# LCD.net
KiCad netlist of a schematic drawn in Altium Designer
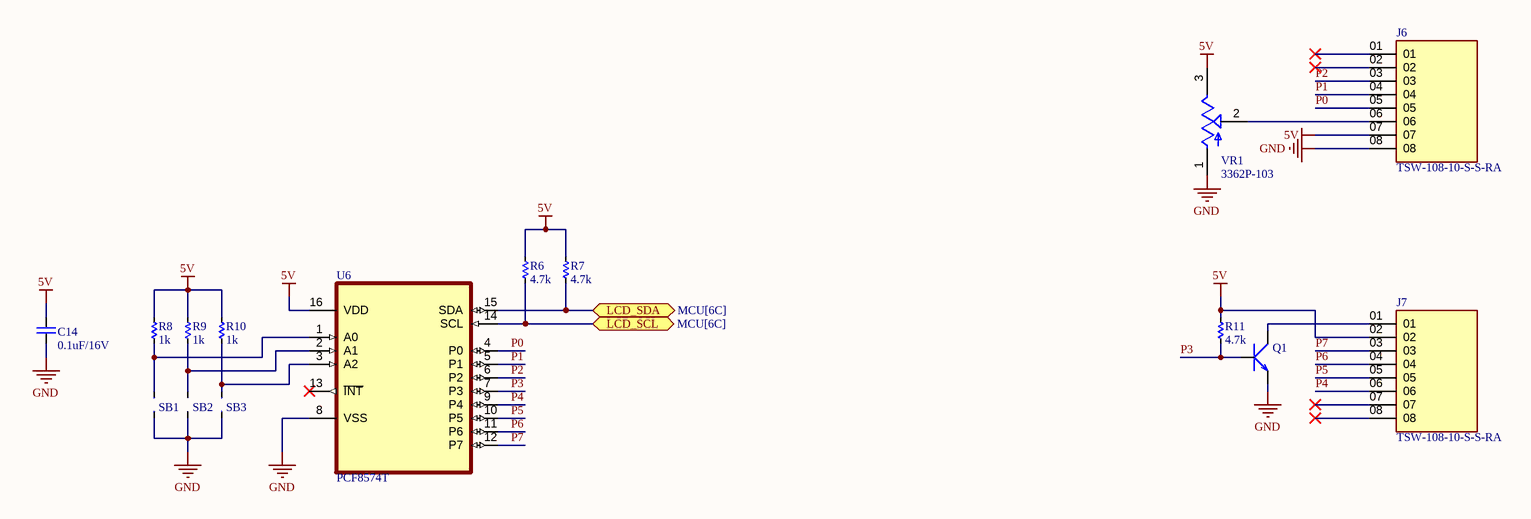
[diagram p0: LCD.SchDoc]

(export (version "E")
  (design (tool "Eeschema 10.0.6"))
  (components
    (comp (ref "C14")
      (value "0.1uF/16V")
      (footprint "CAP_C_1608X80")
      (description "CAP_Chip")
      (libsource (lib "BTL_SCHLIB") (part "CAP_SMD"))
    )
    (comp (ref "J6")
      (value "TSW-108-10-S-S-RA")
      (footprint "SAMTEC_TSW-108-10-S-S-RA")
      (description "Connector Header Through Hole, Right Angle 8 position 0.100 (2.54mm)")
      (fields (field (name "MF") "Samtec"))
      (libsource (lib "BTL_SCHLIB") (part "TSW-108-10-S-S-RA"))
    )
    (comp (ref "J7")
      (value "TSW-108-10-S-S-RA")
      (footprint "SAMTEC_TSW-108-10-S-S-RA")
      (description "Connector Header Through Hole, Right Angle 8 position 0.100 (2.54mm)")
      (fields (field (name "MF") "Samtec"))
      (libsource (lib "BTL_SCHLIB") (part "TSW-108-10-S-S-RA"))
    )
    (comp (ref "Q1")
      (value "SMD-TRANSISTORS-NPN-25V-500MW(SOT-23)")
      (footprint "SOT-23")
      (description "Bipolar (BJT) Transistor NPN 25 V 500 mA 150MHz 300 mW Surface Mount SOT-23")
      (fields (field (name "MF") "UMW") (field (name "MP") "S8050"))
      (libsource (lib "BTL_SCHLIB") (part "SMD-TRANSISTORS-NPN-25V-500MW(SOT-23)"))
    )
    (comp (ref "R6")
      (value "4.7k")
      (footprint "RES_C_1608X60")
      (description "RES")
      (libsource (lib "BTL_SCHLIB") (part "RES_SMD"))
    )
    (comp (ref "R7")
      (value "4.7k")
      (footprint "RES_C_1608X60")
      (description "RES")
      (libsource (lib "BTL_SCHLIB") (part "RES_SMD"))
    )
    (comp (ref "R8")
      (value "1k")
      (footprint "RES_C_1608X60")
      (description "RES")
      (libsource (lib "BTL_SCHLIB") (part "RES_SMD"))
    )
    (comp (ref "R9")
      (value "1k")
      (footprint "RES_C_1608X60")
      (description "RES")
      (libsource (lib "BTL_SCHLIB") (part "RES_SMD"))
    )
    (comp (ref "R10")
      (value "1k")
      (footprint "RES_C_1608X60")
      (description "RES")
      (libsource (lib "BTL_SCHLIB") (part "RES_SMD"))
    )
    (comp (ref "R11")
      (value "4.7k")
      (footprint "RES_C_1608X60")
      (description "RES")
      (libsource (lib "BTL_SCHLIB") (part "RES_SMD"))
    )
    (comp (ref "SB1")
      (value "JUMPER")
      (footprint "JUMPER_1608")
      (libsource (lib "BTL_SCHLIB") (part "JUMPER"))
    )
    (comp (ref "SB2")
      (value "JUMPER")
      (footprint "JUMPER_1608")
      (libsource (lib "BTL_SCHLIB") (part "JUMPER"))
    )
    (comp (ref "SB3")
      (value "JUMPER")
      (footprint "JUMPER_1608")
      (libsource (lib "BTL_SCHLIB") (part "JUMPER"))
    )
    (comp (ref "U6")
      (value "PCF8574T")
      (footprint "SOIC127P1032X265-16N")
      (description "I/O Expander 8 IÂ²C 100 kHz 20-SSOP")
      (fields (field (name "MF") "NXP Semiconductors"))
      (libsource (lib "BTL_SCHLIB") (part "PCF8574T"))
    )
    (comp (ref "VR1")
      (value "3362P-103")
      (footprint "TRIM_3362P-103")
      (description "10 kOhms 0.5W, 1/2W PC Pins Through Hole Trimmer Potentiometer Cermet 1 Turn Top Finger Adjustment")
      (fields (field (name "MF") "Bourns"))
      (libsource (lib "BTL_SCHLIB") (part "3362P-103"))
    )
  )
  (nets
    (net (code "1") (name "/LCD_SCL") (class "Default")
      (node (ref "R6") (pin "1") (pinfunction "1_1") (pintype "passive"))
      (node (ref "U6") (pin "14") (pinfunction "SCL_14") (pintype "input"))
    )
    (net (code "2") (name "/LCD_SDA") (class "Default")
      (node (ref "R7") (pin "1") (pinfunction "1_1") (pintype "passive"))
      (node (ref "U6") (pin "15") (pinfunction "SDA_15") (pintype "bidirectional"))
    )
    (net (code "3") (name "/P0") (class "Default")
      (node (ref "J6") (pin "05") (pinfunction "05_05") (pintype "passive"))
      (node (ref "U6") (pin "4") (pinfunction "P0_4") (pintype "bidirectional"))
    )
    (net (code "4") (name "/P1") (class "Default")
      (node (ref "J6") (pin "04") (pinfunction "04_04") (pintype "passive"))
      (node (ref "U6") (pin "5") (pinfunction "P1_5") (pintype "bidirectional"))
    )
    (net (code "5") (name "/P2") (class "Default")
      (node (ref "J6") (pin "03") (pinfunction "03_03") (pintype "passive"))
      (node (ref "U6") (pin "6") (pinfunction "P2_6") (pintype "bidirectional"))
    )
    (net (code "6") (name "/P3") (class "Default")
      (node (ref "Q1") (pin "1") (pinfunction "B_1") (pintype "passive"))
      (node (ref "R11") (pin "1") (pinfunction "1_1") (pintype "passive"))
      (node (ref "U6") (pin "7") (pinfunction "P3_7") (pintype "bidirectional"))
    )
    (net (code "7") (name "/P4") (class "Default")
      (node (ref "J7") (pin "06") (pinfunction "06_06") (pintype "passive"))
      (node (ref "U6") (pin "9") (pinfunction "P4_9") (pintype "bidirectional"))
    )
    (net (code "8") (name "/P5") (class "Default")
      (node (ref "J7") (pin "05") (pinfunction "05_05") (pintype "passive"))
      (node (ref "U6") (pin "10") (pinfunction "P5_10") (pintype "bidirectional"))
    )
    (net (code "9") (name "/P6") (class "Default")
      (node (ref "J7") (pin "04") (pinfunction "04_04") (pintype "passive"))
      (node (ref "U6") (pin "11") (pinfunction "P6_11") (pintype "bidirectional"))
    )
    (net (code "10") (name "/P7") (class "Default")
      (node (ref "J7") (pin "03") (pinfunction "03_03") (pintype "passive"))
      (node (ref "U6") (pin "12") (pinfunction "P7_12") (pintype "bidirectional"))
    )
    (net (code "11") (name "5V") (class "Default")
      (node (ref "C14") (pin "2") (pinfunction "2_2") (pintype "passive"))
      (node (ref "J6") (pin "07") (pinfunction "07_07") (pintype "passive"))
      (node (ref "J7") (pin "02") (pinfunction "02_02") (pintype "passive"))
      (node (ref "R10") (pin "2") (pinfunction "2_2") (pintype "passive"))
      (node (ref "R11") (pin "2") (pinfunction "2_2") (pintype "passive"))
      (node (ref "R6") (pin "2") (pinfunction "2_2") (pintype "passive"))
      (node (ref "R7") (pin "2") (pinfunction "2_2") (pintype "passive"))
      (node (ref "R8") (pin "2") (pinfunction "2_2") (pintype "passive"))
      (node (ref "R9") (pin "2") (pinfunction "2_2") (pintype "passive"))
      (node (ref "U6") (pin "16") (pinfunction "VDD_16") (pintype "power_in"))
      (node (ref "VR1") (pin "3") (pinfunction "CW_3") (pintype "passive"))
    )
    (net (code "12") (name "GND") (class "Default")
      (node (ref "C14") (pin "1") (pinfunction "1_1") (pintype "passive"))
      (node (ref "J6") (pin "08") (pinfunction "08_08") (pintype "passive"))
      (node (ref "Q1") (pin "2") (pinfunction "E_2") (pintype "passive"))
      (node (ref "SB1") (pin "1") (pinfunction "1_1") (pintype "passive"))
      (node (ref "SB2") (pin "1") (pinfunction "1_1") (pintype "passive"))
      (node (ref "SB3") (pin "1") (pinfunction "1_1") (pintype "passive"))
      (node (ref "U6") (pin "8") (pinfunction "VSS_8") (pintype "passive"))
      (node (ref "VR1") (pin "1") (pinfunction "CCW_1") (pintype "passive"))
    )
    (net (code "13") (name "Net-(Q1-C)") (class "Default")
      (node (ref "J7") (pin "01") (pinfunction "01_01") (pintype "passive"))
      (node (ref "Q1") (pin "3") (pinfunction "C_3") (pintype "passive"))
    )
    (net (code "14") (name "Net-(U6-A0)") (class "Default")
      (node (ref "R8") (pin "1") (pinfunction "1_1") (pintype "passive"))
      (node (ref "SB1") (pin "2") (pinfunction "2_2") (pintype "passive"))
      (node (ref "U6") (pin "1") (pinfunction "A0_1") (pintype "input"))
    )
    (net (code "15") (name "Net-(U6-A1)") (class "Default")
      (node (ref "R9") (pin "1") (pinfunction "1_1") (pintype "passive"))
      (node (ref "SB2") (pin "2") (pinfunction "2_2") (pintype "passive"))
      (node (ref "U6") (pin "2") (pinfunction "A1_2") (pintype "input"))
    )
    (net (code "16") (name "Net-(U6-A2)") (class "Default")
      (node (ref "R10") (pin "1") (pinfunction "1_1") (pintype "passive"))
      (node (ref "SB3") (pin "2") (pinfunction "2_2") (pintype "passive"))
      (node (ref "U6") (pin "3") (pinfunction "A2_3") (pintype "input"))
    )
    (net (code "17") (name "Net-(VR1-WIPER)") (class "Default")
      (node (ref "J6") (pin "06") (pinfunction "06_06") (pintype "passive"))
      (node (ref "VR1") (pin "2") (pinfunction "WIPER_2") (pintype "passive"))
    )
    (net (code "18") (name "unconnected-(J6-Pad01)") (class "Default")
      (node (ref "J6") (pin "01") (pinfunction "01_01") (pintype "passive+no_connect"))
    )
    (net (code "19") (name "unconnected-(J6-Pad02)") (class "Default")
      (node (ref "J6") (pin "02") (pinfunction "02_02") (pintype "passive+no_connect"))
    )
    (net (code "20") (name "unconnected-(J7-Pad07)") (class "Default")
      (node (ref "J7") (pin "07") (pinfunction "07_07") (pintype "passive+no_connect"))
    )
    (net (code "21") (name "unconnected-(J7-Pad08)") (class "Default")
      (node (ref "J7") (pin "08") (pinfunction "08_08") (pintype "passive+no_connect"))
    )
    (net (code "22") (name "unconnected-(U6-~{INT}-Pad13)") (class "Default")
      (node (ref "U6") (pin "13") (pinfunction "~{INT}_13") (pintype "output+no_connect"))
    )
  )
)
